# Amp_op.net
KiCad netlist of a schematic drawn in Altium Designer
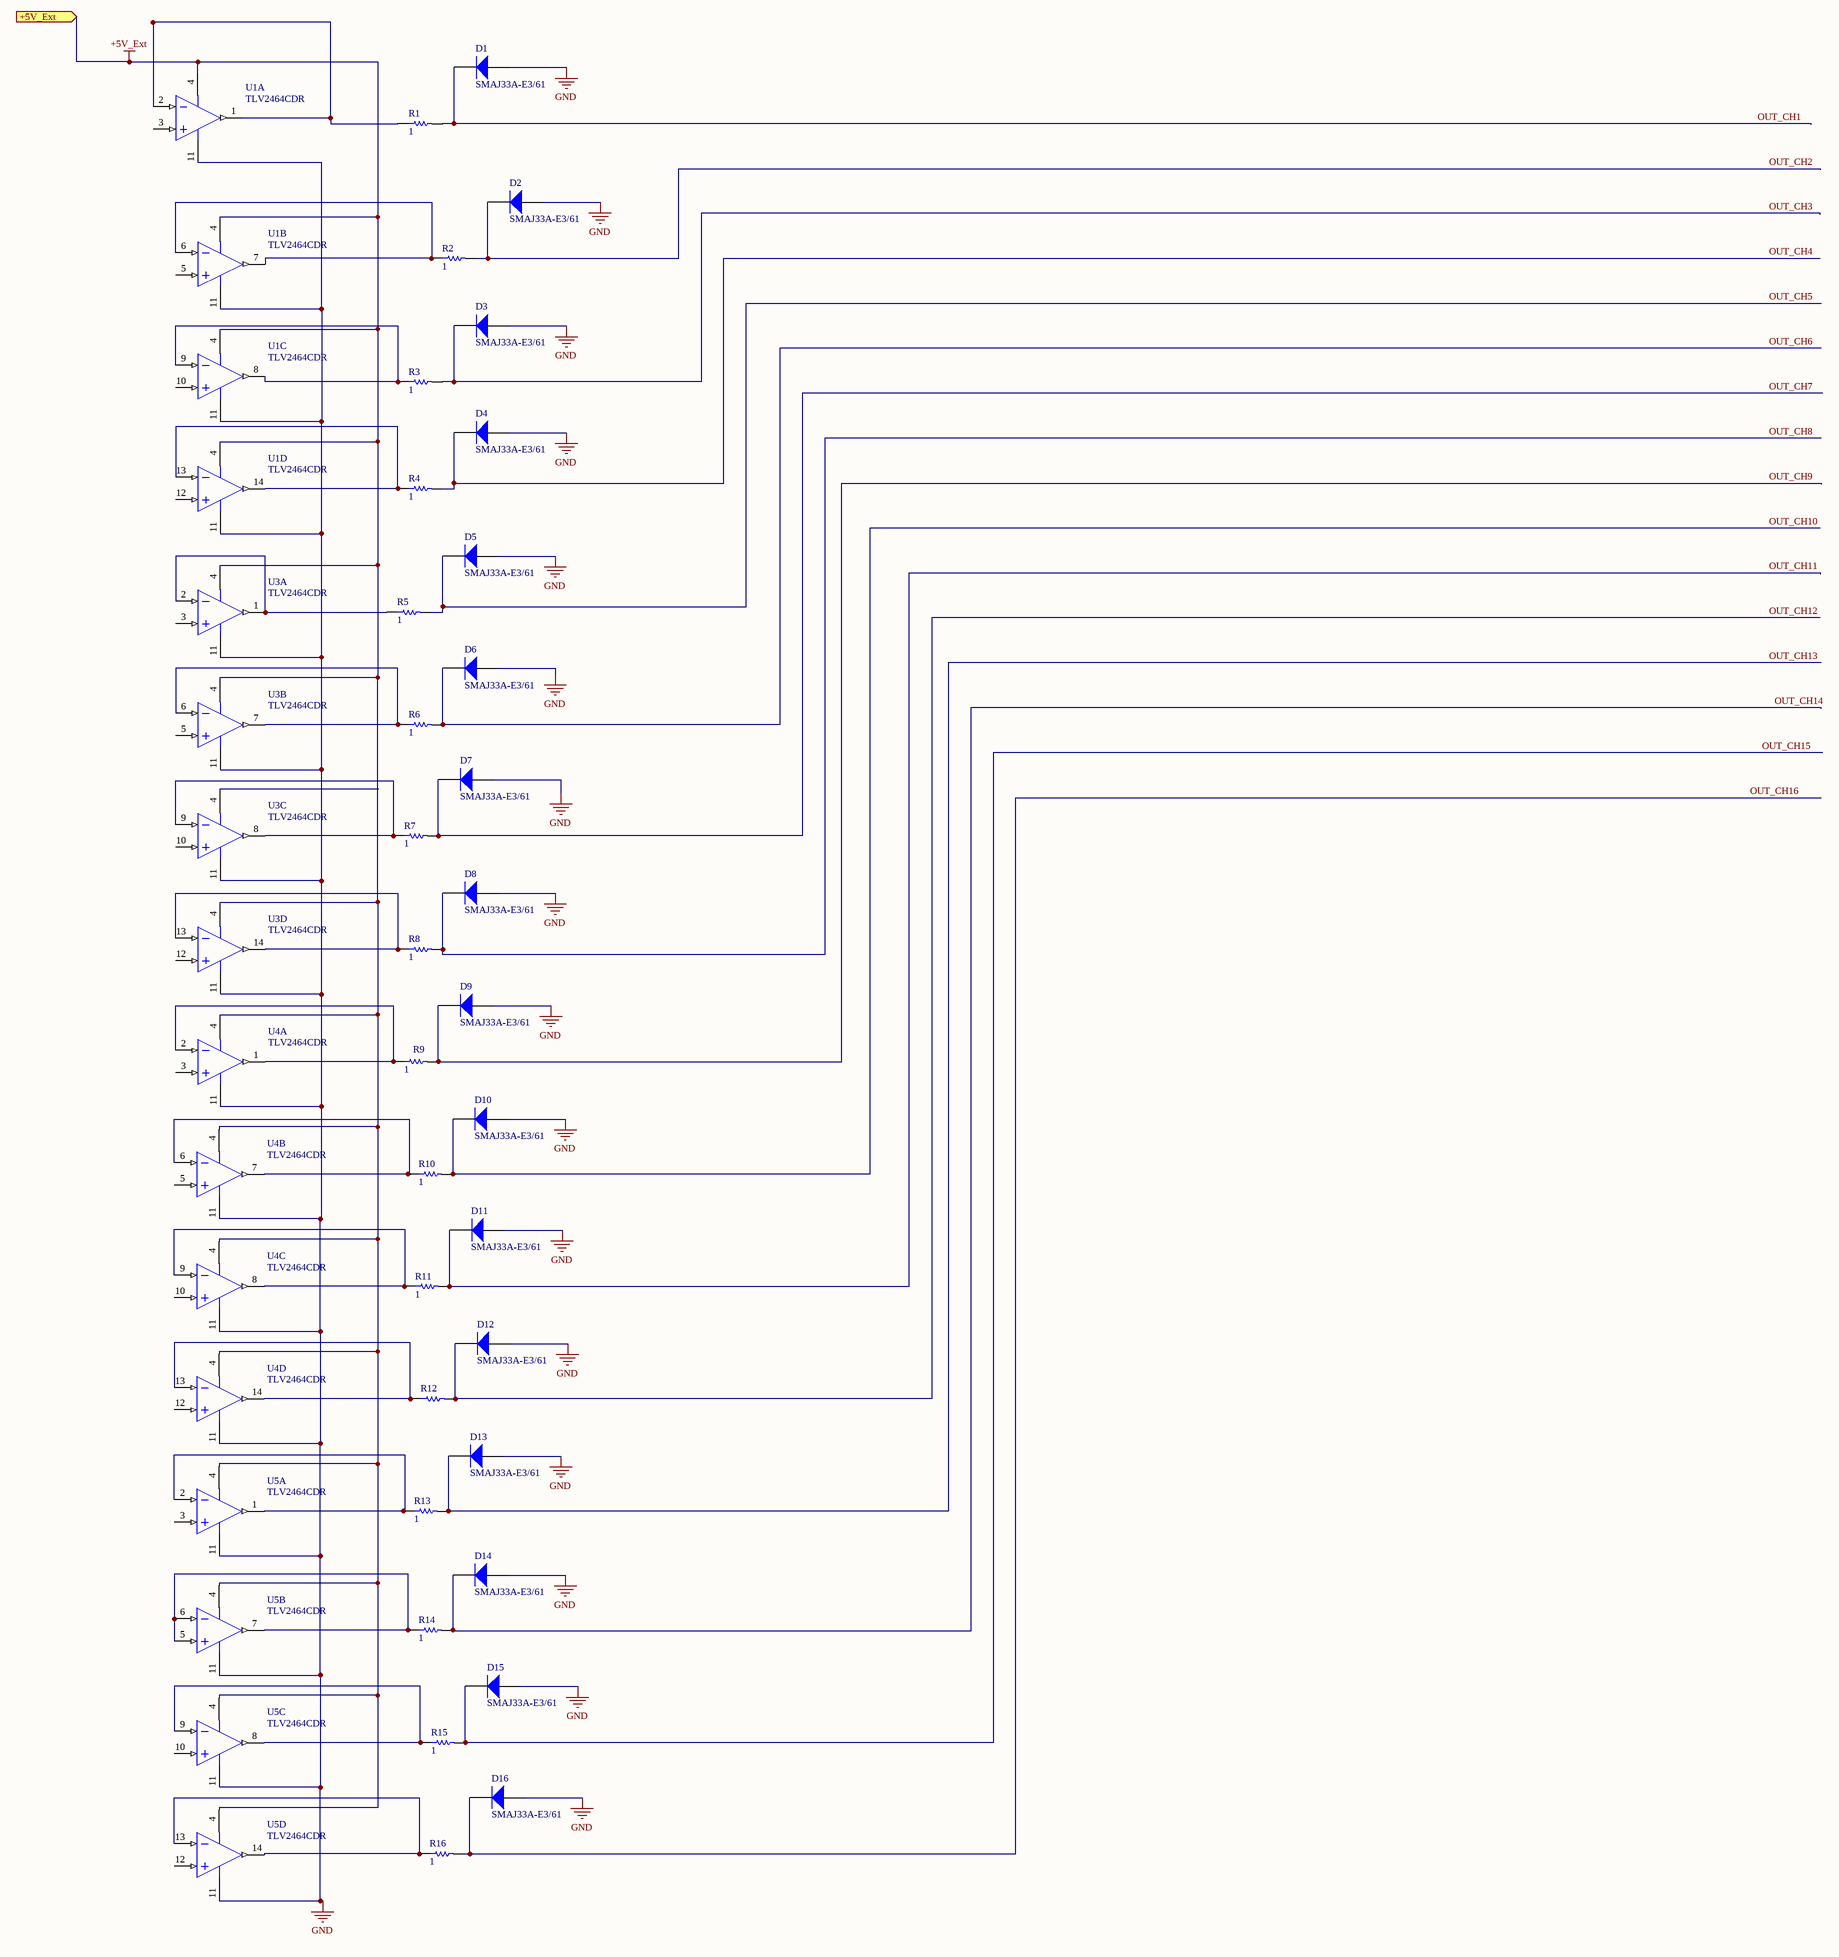
[diagram p0: Amp_op.SchDoc]

(export (version "E")
  (design (tool "Eeschema 10.0.6"))
  (components
    (comp (ref "D1")
      (value "SMAJ33A-E3/61")
      (footprint "VISH-DO-214AC-2_L")
      (fields (field (name "MANUFACTURER") "Vishay Semiconductor"))
      (libsource (lib "Altium Content Vault") (part "VISH-K1A2-2"))
    )
    (comp (ref "D2")
      (value "SMAJ33A-E3/61")
      (footprint "VISH-DO-214AC-2_L")
      (fields (field (name "MANUFACTURER") "Vishay Semiconductor"))
      (libsource (lib "Altium Content Vault") (part "VISH-K1A2-2"))
    )
    (comp (ref "D3")
      (value "SMAJ33A-E3/61")
      (footprint "VISH-DO-214AC-2_L")
      (fields (field (name "MANUFACTURER") "Vishay Semiconductor"))
      (libsource (lib "Altium Content Vault") (part "VISH-K1A2-2"))
    )
    (comp (ref "D4")
      (value "SMAJ33A-E3/61")
      (footprint "VISH-DO-214AC-2_L")
      (fields (field (name "MANUFACTURER") "Vishay Semiconductor"))
      (libsource (lib "Altium Content Vault") (part "VISH-K1A2-2"))
    )
    (comp (ref "D5")
      (value "SMAJ33A-E3/61")
      (footprint "VISH-DO-214AC-2_L")
      (fields (field (name "MANUFACTURER") "Vishay Semiconductor"))
      (libsource (lib "Altium Content Vault") (part "VISH-K1A2-2"))
    )
    (comp (ref "D6")
      (value "SMAJ33A-E3/61")
      (footprint "VISH-DO-214AC-2_L")
      (fields (field (name "MANUFACTURER") "Vishay Semiconductor"))
      (libsource (lib "Altium Content Vault") (part "VISH-K1A2-2"))
    )
    (comp (ref "D7")
      (value "SMAJ33A-E3/61")
      (footprint "VISH-DO-214AC-2_L")
      (fields (field (name "MANUFACTURER") "Vishay Semiconductor"))
      (libsource (lib "Altium Content Vault") (part "VISH-K1A2-2"))
    )
    (comp (ref "D8")
      (value "SMAJ33A-E3/61")
      (footprint "VISH-DO-214AC-2_L")
      (fields (field (name "MANUFACTURER") "Vishay Semiconductor"))
      (libsource (lib "Altium Content Vault") (part "VISH-K1A2-2"))
    )
    (comp (ref "D9")
      (value "SMAJ33A-E3/61")
      (footprint "VISH-DO-214AC-2_L")
      (fields (field (name "MANUFACTURER") "Vishay Semiconductor"))
      (libsource (lib "Altium Content Vault") (part "VISH-K1A2-2"))
    )
    (comp (ref "D10")
      (value "SMAJ33A-E3/61")
      (footprint "VISH-DO-214AC-2_L")
      (fields (field (name "MANUFACTURER") "Vishay Semiconductor"))
      (libsource (lib "Altium Content Vault") (part "VISH-K1A2-2"))
    )
    (comp (ref "D11")
      (value "SMAJ33A-E3/61")
      (footprint "VISH-DO-214AC-2_L")
      (fields (field (name "MANUFACTURER") "Vishay Semiconductor"))
      (libsource (lib "Altium Content Vault") (part "VISH-K1A2-2"))
    )
    (comp (ref "D12")
      (value "SMAJ33A-E3/61")
      (footprint "VISH-DO-214AC-2_L")
      (fields (field (name "MANUFACTURER") "Vishay Semiconductor"))
      (libsource (lib "Altium Content Vault") (part "VISH-K1A2-2"))
    )
    (comp (ref "D13")
      (value "SMAJ33A-E3/61")
      (footprint "VISH-DO-214AC-2_L")
      (fields (field (name "MANUFACTURER") "Vishay Semiconductor"))
      (libsource (lib "Altium Content Vault") (part "VISH-K1A2-2"))
    )
    (comp (ref "D14")
      (value "SMAJ33A-E3/61")
      (footprint "VISH-DO-214AC-2_L")
      (fields (field (name "MANUFACTURER") "Vishay Semiconductor"))
      (libsource (lib "Altium Content Vault") (part "VISH-K1A2-2"))
    )
    (comp (ref "D15")
      (value "SMAJ33A-E3/61")
      (footprint "VISH-DO-214AC-2_L")
      (fields (field (name "MANUFACTURER") "Vishay Semiconductor"))
      (libsource (lib "Altium Content Vault") (part "VISH-K1A2-2"))
    )
    (comp (ref "D16")
      (value "SMAJ33A-E3/61")
      (footprint "VISH-DO-214AC-2_L")
      (fields (field (name "MANUFACTURER") "Vishay Semiconductor"))
      (libsource (lib "Altium Content Vault") (part "VISH-K1A2-2"))
    )
    (comp (ref "R1")
      (value "1")
      (description "Resistor")
      (libsource (lib "Simulation Generic Components") (part "Resistor"))
    )
    (comp (ref "R2")
      (value "1")
      (description "Resistor")
      (libsource (lib "Simulation Generic Components") (part "Resistor"))
    )
    (comp (ref "R3")
      (value "1")
      (description "Resistor")
      (libsource (lib "Simulation Generic Components") (part "Resistor"))
    )
    (comp (ref "R4")
      (value "1")
      (description "Resistor")
      (libsource (lib "Simulation Generic Components") (part "Resistor"))
    )
    (comp (ref "R5")
      (value "1")
      (description "Resistor")
      (libsource (lib "Simulation Generic Components") (part "Resistor"))
    )
    (comp (ref "R6")
      (value "1")
      (description "Resistor")
      (libsource (lib "Simulation Generic Components") (part "Resistor"))
    )
    (comp (ref "R7")
      (value "1")
      (description "Resistor")
      (libsource (lib "Simulation Generic Components") (part "Resistor"))
    )
    (comp (ref "R8")
      (value "1")
      (description "Resistor")
      (libsource (lib "Simulation Generic Components") (part "Resistor"))
    )
    (comp (ref "R9")
      (value "1")
      (description "Resistor")
      (libsource (lib "Simulation Generic Components") (part "Resistor"))
    )
    (comp (ref "R10")
      (value "1")
      (description "Resistor")
      (libsource (lib "Simulation Generic Components") (part "Resistor"))
    )
    (comp (ref "R11")
      (value "1")
      (description "Resistor")
      (libsource (lib "Simulation Generic Components") (part "Resistor"))
    )
    (comp (ref "R12") (value "Resistor") (libsource (lib "Simulation Generic Components") (part "Resistor")))
    (comp (ref "R13")
      (value "1")
      (description "Resistor")
      (libsource (lib "Simulation Generic Components") (part "Resistor"))
    )
    (comp (ref "R14")
      (value "1")
      (description "Resistor")
      (libsource (lib "Simulation Generic Components") (part "Resistor"))
    )
    (comp (ref "R15")
      (value "1")
      (description "Resistor")
      (libsource (lib "Simulation Generic Components") (part "Resistor"))
    )
    (comp (ref "R16")
      (value "1")
      (description "Resistor")
      (libsource (lib "Simulation Generic Components") (part "Resistor"))
    )
    (comp (ref "U1")
      (value "TLV2464CDR")
      (footprint "D0014A_N")
      (fields (field (name "MANUFACTURER") "Texas Instruments"))
      (libsource (lib "Altium Content Vault") (part "TI-TLV2464X-XX14"))
    )
    (comp (ref "U3")
      (value "TLV2464CDR")
      (footprint "D0014A_N")
      (fields (field (name "MANUFACTURER") "Texas Instruments"))
      (libsource (lib "Altium Content Vault") (part "TI-TLV2464X-XX14"))
    )
    (comp (ref "U4")
      (value "TLV2464CDR")
      (footprint "D0014A_N")
      (fields (field (name "MANUFACTURER") "Texas Instruments"))
      (libsource (lib "Altium Content Vault") (part "TI-TLV2464X-XX14"))
    )
    (comp (ref "U5")
      (value "TLV2464CDR")
      (footprint "D0014A_N")
      (fields (field (name "MANUFACTURER") "Texas Instruments"))
      (libsource (lib "Altium Content Vault") (part "TI-TLV2464X-XX14"))
    )
  )
  (nets
    (net (code "1") (name "+5V_Ext") (class "Default")
      (node (ref "U1") (pin "4") (pinfunction "VDD+_4") (pintype "power_in"))
      (node (ref "U3") (pin "4") (pinfunction "VDD+_4") (pintype "power_in"))
      (node (ref "U4") (pin "4") (pinfunction "VDD+_4") (pintype "power_in"))
      (node (ref "U5") (pin "4") (pinfunction "VDD+_4") (pintype "power_in"))
    )
    (net (code "2") (name "/OUT_CH1") (class "Default")
      (node (ref "D1") (pin "1") (pinfunction "K_1") (pintype "passive"))
      (node (ref "R1") (pin "2") (pinfunction "2_2") (pintype "passive"))
    )
    (net (code "3") (name "/OUT_CH2") (class "Default")
      (node (ref "D2") (pin "1") (pinfunction "K_1") (pintype "passive"))
      (node (ref "R2") (pin "2") (pinfunction "2_2") (pintype "passive"))
    )
    (net (code "4") (name "/OUT_CH3") (class "Default")
      (node (ref "D3") (pin "1") (pinfunction "K_1") (pintype "passive"))
      (node (ref "R3") (pin "2") (pinfunction "2_2") (pintype "passive"))
    )
    (net (code "5") (name "/OUT_CH4") (class "Default")
      (node (ref "D4") (pin "1") (pinfunction "K_1") (pintype "passive"))
      (node (ref "R4") (pin "2") (pinfunction "2_2") (pintype "passive"))
    )
    (net (code "6") (name "/OUT_CH5") (class "Default")
      (node (ref "D5") (pin "1") (pinfunction "K_1") (pintype "passive"))
      (node (ref "R5") (pin "2") (pinfunction "2_2") (pintype "passive"))
    )
    (net (code "7") (name "/OUT_CH6") (class "Default")
      (node (ref "D6") (pin "1") (pinfunction "K_1") (pintype "passive"))
      (node (ref "R6") (pin "2") (pinfunction "2_2") (pintype "passive"))
    )
    (net (code "8") (name "/OUT_CH7") (class "Default")
      (node (ref "D7") (pin "1") (pinfunction "K_1") (pintype "passive"))
      (node (ref "R7") (pin "2") (pinfunction "2_2") (pintype "passive"))
    )
    (net (code "9") (name "/OUT_CH8") (class "Default")
      (node (ref "D8") (pin "1") (pinfunction "K_1") (pintype "passive"))
      (node (ref "R8") (pin "2") (pinfunction "2_2") (pintype "passive"))
    )
    (net (code "10") (name "/OUT_CH9") (class "Default")
      (node (ref "D9") (pin "1") (pinfunction "K_1") (pintype "passive"))
      (node (ref "R9") (pin "2") (pinfunction "2_2") (pintype "passive"))
    )
    (net (code "11") (name "/OUT_CH10") (class "Default")
      (node (ref "D10") (pin "1") (pinfunction "K_1") (pintype "passive"))
      (node (ref "R10") (pin "2") (pinfunction "2_2") (pintype "passive"))
    )
    (net (code "12") (name "/OUT_CH11") (class "Default")
      (node (ref "D11") (pin "1") (pinfunction "K_1") (pintype "passive"))
      (node (ref "R11") (pin "2") (pinfunction "2_2") (pintype "passive"))
    )
    (net (code "13") (name "/OUT_CH12") (class "Default")
      (node (ref "D12") (pin "1") (pinfunction "K_1") (pintype "passive"))
      (node (ref "R12") (pin "2") (pinfunction "2_2") (pintype "passive"))
    )
    (net (code "14") (name "/OUT_CH13") (class "Default")
      (node (ref "D13") (pin "1") (pinfunction "K_1") (pintype "passive"))
      (node (ref "R13") (pin "2") (pinfunction "2_2") (pintype "passive"))
    )
    (net (code "15") (name "/OUT_CH14") (class "Default")
      (node (ref "D14") (pin "1") (pinfunction "K_1") (pintype "passive"))
      (node (ref "R14") (pin "2") (pinfunction "2_2") (pintype "passive"))
    )
    (net (code "16") (name "/OUT_CH15") (class "Default")
      (node (ref "D15") (pin "1") (pinfunction "K_1") (pintype "passive"))
      (node (ref "R15") (pin "2") (pinfunction "2_2") (pintype "passive"))
    )
    (net (code "17") (name "/OUT_CH16") (class "Default")
      (node (ref "D16") (pin "1") (pinfunction "K_1") (pintype "passive"))
      (node (ref "R16") (pin "2") (pinfunction "2_2") (pintype "passive"))
    )
    (net (code "18") (name "GND") (class "Default")
      (node (ref "D1") (pin "2") (pinfunction "A_2") (pintype "passive"))
      (node (ref "D10") (pin "2") (pinfunction "A_2") (pintype "passive"))
      (node (ref "D11") (pin "2") (pinfunction "A_2") (pintype "passive"))
      (node (ref "D12") (pin "2") (pinfunction "A_2") (pintype "passive"))
      (node (ref "D13") (pin "2") (pinfunction "A_2") (pintype "passive"))
      (node (ref "D14") (pin "2") (pinfunction "A_2") (pintype "passive"))
      (node (ref "D15") (pin "2") (pinfunction "A_2") (pintype "passive"))
      (node (ref "D16") (pin "2") (pinfunction "A_2") (pintype "passive"))
      (node (ref "D2") (pin "2") (pinfunction "A_2") (pintype "passive"))
      (node (ref "D3") (pin "2") (pinfunction "A_2") (pintype "passive"))
      (node (ref "D4") (pin "2") (pinfunction "A_2") (pintype "passive"))
      (node (ref "D5") (pin "2") (pinfunction "A_2") (pintype "passive"))
      (node (ref "D6") (pin "2") (pinfunction "A_2") (pintype "passive"))
      (node (ref "D7") (pin "2") (pinfunction "A_2") (pintype "passive"))
      (node (ref "D8") (pin "2") (pinfunction "A_2") (pintype "passive"))
      (node (ref "D9") (pin "2") (pinfunction "A_2") (pintype "passive"))
      (node (ref "U3") (pin "11") (pinfunction "GND_11") (pintype "power_in"))
      (node (ref "U4") (pin "11") (pinfunction "GND_11") (pintype "power_in"))
      (node (ref "U5") (pin "11") (pinfunction "GND_11") (pintype "power_in"))
    )
    (net (code "19") (name "Net-(U1A-GND)") (class "Default")
      (node (ref "U1") (pin "11") (pinfunction "GND_11") (pintype "power_in"))
      (node (ref "U3") (pin "11") (pinfunction "GND_11") (pintype "power_in"))
    )
    (net (code "20") (name "Net-(U1A-IN1-)") (class "Default")
      (node (ref "R1") (pin "1") (pinfunction "1_1") (pintype "passive"))
      (node (ref "U1") (pin "1") (pinfunction "OUT1_1") (pintype "output"))
      (node (ref "U1") (pin "2") (pinfunction "IN1-_2") (pintype "input"))
    )
    (net (code "21") (name "Net-(U1B-IN2-)") (class "Default")
      (node (ref "R2") (pin "1") (pinfunction "1_1") (pintype "passive"))
      (node (ref "U1") (pin "6") (pinfunction "IN2-_6") (pintype "input"))
      (node (ref "U1") (pin "7") (pinfunction "OUT2_7") (pintype "output"))
    )
    (net (code "22") (name "Net-(U1C-IN3-)") (class "Default")
      (node (ref "R3") (pin "1") (pinfunction "1_1") (pintype "passive"))
      (node (ref "U1") (pin "8") (pinfunction "OUT3_8") (pintype "output"))
      (node (ref "U1") (pin "9") (pinfunction "IN3-_9") (pintype "input"))
    )
    (net (code "23") (name "Net-(U1D-IN4-)") (class "Default")
      (node (ref "R4") (pin "1") (pinfunction "1_1") (pintype "passive"))
      (node (ref "U1") (pin "13") (pinfunction "IN4-_13") (pintype "input"))
      (node (ref "U1") (pin "14") (pinfunction "OUT4_14") (pintype "output"))
    )
    (net (code "24") (name "Net-(U3A-IN1-)") (class "Default")
      (node (ref "R5") (pin "1") (pinfunction "1_1") (pintype "passive"))
      (node (ref "U3") (pin "1") (pinfunction "OUT1_1") (pintype "output"))
      (node (ref "U3") (pin "2") (pinfunction "IN1-_2") (pintype "input"))
    )
    (net (code "25") (name "Net-(U3B-IN2-)") (class "Default")
      (node (ref "R6") (pin "1") (pinfunction "1_1") (pintype "passive"))
      (node (ref "U3") (pin "6") (pinfunction "IN2-_6") (pintype "input"))
      (node (ref "U3") (pin "7") (pinfunction "OUT2_7") (pintype "output"))
    )
    (net (code "26") (name "Net-(U3C-IN3-)") (class "Default")
      (node (ref "R7") (pin "1") (pinfunction "1_1") (pintype "passive"))
      (node (ref "U3") (pin "8") (pinfunction "OUT3_8") (pintype "output"))
      (node (ref "U3") (pin "9") (pinfunction "IN3-_9") (pintype "input"))
    )
    (net (code "27") (name "Net-(U3D-IN4-)") (class "Default")
      (node (ref "R8") (pin "1") (pinfunction "1_1") (pintype "passive"))
      (node (ref "U3") (pin "13") (pinfunction "IN4-_13") (pintype "input"))
      (node (ref "U3") (pin "14") (pinfunction "OUT4_14") (pintype "output"))
    )
    (net (code "28") (name "Net-(U4A-IN1-)") (class "Default")
      (node (ref "R9") (pin "1") (pinfunction "1_1") (pintype "passive"))
      (node (ref "U4") (pin "1") (pinfunction "OUT1_1") (pintype "output"))
      (node (ref "U4") (pin "2") (pinfunction "IN1-_2") (pintype "input"))
    )
    (net (code "29") (name "Net-(U4B-IN2-)") (class "Default")
      (node (ref "R10") (pin "1") (pinfunction "1_1") (pintype "passive"))
      (node (ref "U4") (pin "6") (pinfunction "IN2-_6") (pintype "input"))
      (node (ref "U4") (pin "7") (pinfunction "OUT2_7") (pintype "output"))
    )
    (net (code "30") (name "Net-(U4C-IN3-)") (class "Default")
      (node (ref "R11") (pin "1") (pinfunction "1_1") (pintype "passive"))
      (node (ref "U4") (pin "8") (pinfunction "OUT3_8") (pintype "output"))
      (node (ref "U4") (pin "9") (pinfunction "IN3-_9") (pintype "input"))
    )
    (net (code "31") (name "Net-(U4D-IN4-)") (class "Default")
      (node (ref "R12") (pin "1") (pinfunction "1_1") (pintype "passive"))
      (node (ref "U4") (pin "13") (pinfunction "IN4-_13") (pintype "input"))
      (node (ref "U4") (pin "14") (pinfunction "OUT4_14") (pintype "output"))
    )
    (net (code "32") (name "Net-(U5A-IN1-)") (class "Default")
      (node (ref "R13") (pin "1") (pinfunction "1_1") (pintype "passive"))
      (node (ref "U5") (pin "1") (pinfunction "OUT1_1") (pintype "output"))
      (node (ref "U5") (pin "2") (pinfunction "IN1-_2") (pintype "input"))
    )
    (net (code "33") (name "Net-(U5B-IN2+)") (class "Default")
      (node (ref "R14") (pin "1") (pinfunction "1_1") (pintype "passive"))
      (node (ref "U5") (pin "5") (pinfunction "IN2+_5") (pintype "input"))
      (node (ref "U5") (pin "6") (pinfunction "IN2-_6") (pintype "input"))
      (node (ref "U5") (pin "7") (pinfunction "OUT2_7") (pintype "output"))
    )
    (net (code "34") (name "Net-(U5C-IN3-)") (class "Default")
      (node (ref "R15") (pin "1") (pinfunction "1_1") (pintype "passive"))
      (node (ref "U5") (pin "8") (pinfunction "OUT3_8") (pintype "output"))
      (node (ref "U5") (pin "9") (pinfunction "IN3-_9") (pintype "input"))
    )
    (net (code "35") (name "Net-(U5D-IN4-)") (class "Default")
      (node (ref "R16") (pin "1") (pinfunction "1_1") (pintype "passive"))
      (node (ref "U5") (pin "13") (pinfunction "IN4-_13") (pintype "input"))
      (node (ref "U5") (pin "14") (pinfunction "OUT4_14") (pintype "output"))
    )
    (net (code "36") (name "unconnected-(U1A-IN1+-Pad3)") (class "Default")
      (node (ref "U1") (pin "3") (pinfunction "IN1+_3") (pintype "input"))
    )
    (net (code "37") (name "unconnected-(U1B-IN2+-Pad5)") (class "Default")
      (node (ref "U1") (pin "5") (pinfunction "IN2+_5") (pintype "input"))
    )
    (net (code "38") (name "unconnected-(U1C-IN3+-Pad10)") (class "Default")
      (node (ref "U1") (pin "10") (pinfunction "IN3+_10") (pintype "input"))
    )
    (net (code "39") (name "unconnected-(U1D-IN4+-Pad12)") (class "Default")
      (node (ref "U1") (pin "12") (pinfunction "IN4+_12") (pintype "input"))
    )
    (net (code "40") (name "unconnected-(U3A-IN1+-Pad3)") (class "Default")
      (node (ref "U3") (pin "3") (pinfunction "IN1+_3") (pintype "input"))
    )
    (net (code "41") (name "unconnected-(U3B-IN2+-Pad5)") (class "Default")
      (node (ref "U3") (pin "5") (pinfunction "IN2+_5") (pintype "input"))
    )
    (net (code "42") (name "unconnected-(U3C-IN3+-Pad10)") (class "Default")
      (node (ref "U3") (pin "10") (pinfunction "IN3+_10") (pintype "input"))
    )
    (net (code "43") (name "unconnected-(U3C-VDD+-Pad4)") (class "Default")
      (node (ref "U3") (pin "4") (pinfunction "VDD+_4") (pintype "power_in"))
    )
    (net (code "44") (name "unconnected-(U3D-IN4+-Pad12)") (class "Default")
      (node (ref "U3") (pin "12") (pinfunction "IN4+_12") (pintype "input"))
    )
    (net (code "45") (name "unconnected-(U4A-IN1+-Pad3)") (class "Default")
      (node (ref "U4") (pin "3") (pinfunction "IN1+_3") (pintype "input"))
    )
    (net (code "46") (name "unconnected-(U4B-IN2+-Pad5)") (class "Default")
      (node (ref "U4") (pin "5") (pinfunction "IN2+_5") (pintype "input"))
    )
    (net (code "47") (name "unconnected-(U4C-IN3+-Pad10)") (class "Default")
      (node (ref "U4") (pin "10") (pinfunction "IN3+_10") (pintype "input"))
    )
    (net (code "48") (name "unconnected-(U4D-IN4+-Pad12)") (class "Default")
      (node (ref "U4") (pin "12") (pinfunction "IN4+_12") (pintype "input"))
    )
    (net (code "49") (name "unconnected-(U5A-IN1+-Pad3)") (class "Default")
      (node (ref "U5") (pin "3") (pinfunction "IN1+_3") (pintype "input"))
    )
    (net (code "50") (name "unconnected-(U5C-IN3+-Pad10)") (class "Default")
      (node (ref "U5") (pin "10") (pinfunction "IN3+_10") (pintype "input"))
    )
    (net (code "51") (name "unconnected-(U5D-IN4+-Pad12)") (class "Default")
      (node (ref "U5") (pin "12") (pinfunction "IN4+_12") (pintype "input"))
    )
  )
)
